# Motor-Driver-30A-1.net
KiCad netlist of a schematic drawn in EAGLE
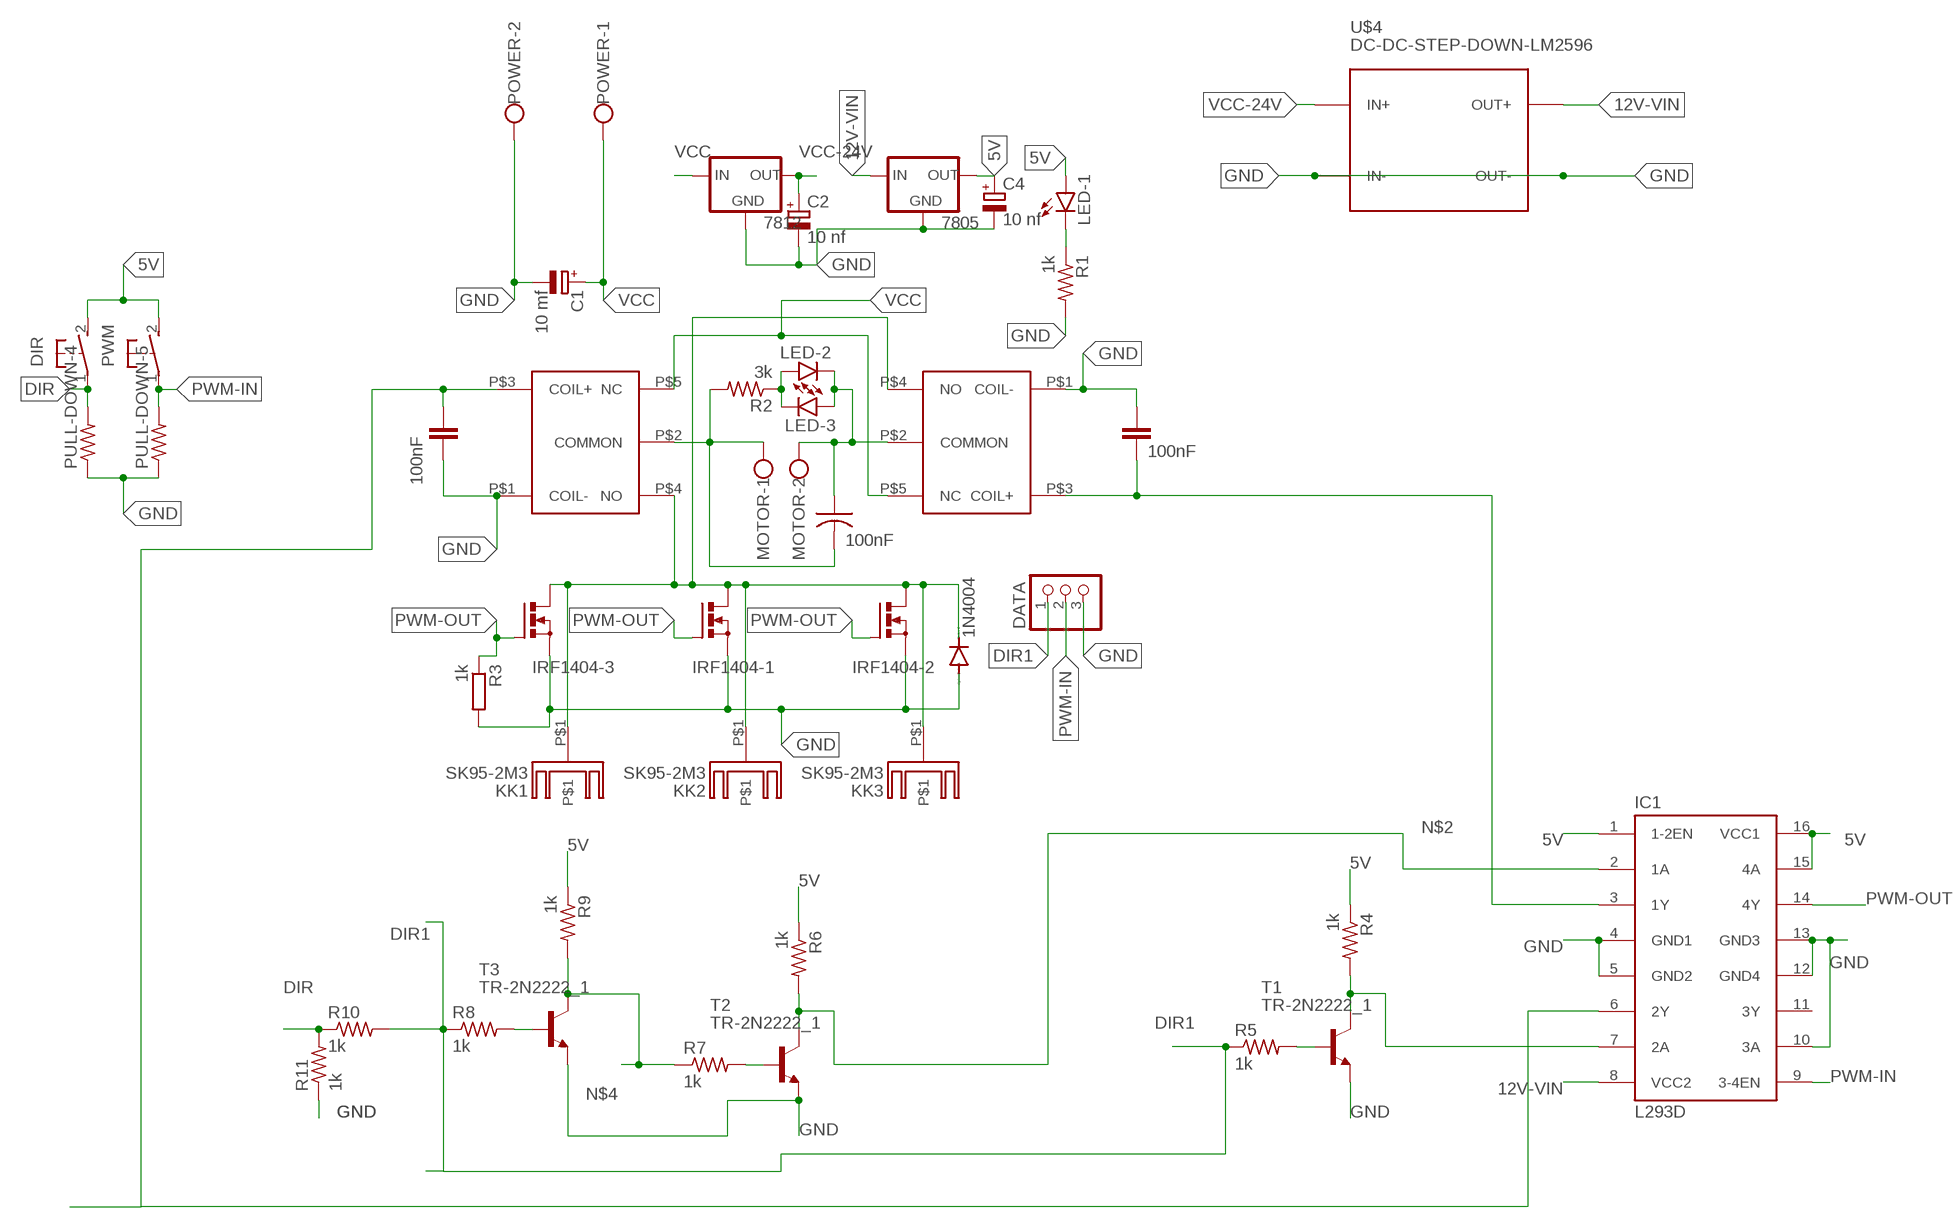
[diagram p0: schematic, sheet 1]

(export (version "E")
  (design (tool "Eeschema 10.0.6"))
  (components
    (comp (ref "7805")
      (value "78XXL")
      (footprint "eagle-import:78XXL")
      (libsource (lib "eagle-import") (part "v-reg_409_78XXL"))
    )
    (comp (ref "7812")
      (value "78XXL")
      (footprint "eagle-import:78XXL")
      (libsource (lib "eagle-import") (part "78XXL"))
    )
    (comp (ref "C1")
      (value "10 mf")
      (footprint "eagle-import:E2,5-7")
      (libsource (lib "eagle-import") (part "CPOL-EUE2.5-7"))
    )
    (comp (ref "C2")
      (value "10 nf")
      (footprint "eagle-import:E2,5-7")
      (libsource (lib "eagle-import") (part "CPOL-EUE2.5-7"))
    )
    (comp (ref "C4")
      (value "10 nf")
      (footprint "eagle-import:E2,5-7")
      (libsource (lib "eagle-import") (part "CPOL-EUE2.5-7"))
    )
    (comp (ref "DATA")
      (value "PINHD-3_DATA")
      (footprint "eagle-import:1X03_DATA")
      (libsource (lib "eagle-import") (part "PINHD-3_DATA"))
    )
    (comp (ref "DIR")
      (value "PUSHBOTTON")
      (footprint "eagle-import:B3F-10XX")
      (libsource (lib "eagle-import") (part "PUSHBOTTON"))
    )
    (comp (ref "IC1")
      (value "L293D")
      (footprint "eagle-import:DIL16")
      (libsource (lib "eagle-import") (part "L293D"))
    )
    (comp (ref "IRF1404-1")
      (value "PMOSFET_NTO220BV")
      (footprint "eagle-import:TO220BV")
      (libsource (lib "eagle-import") (part "PMOSFET_NTO220BV"))
    )
    (comp (ref "IRF1404-2")
      (value "PMOSFET_NTO220BV")
      (footprint "eagle-import:TO220BV")
      (libsource (lib "eagle-import") (part "PMOSFET_NTO220BV"))
    )
    (comp (ref "IRF1404-3")
      (value "PMOSFET_NTO220BV")
      (footprint "eagle-import:TO220BV")
      (libsource (lib "eagle-import") (part "PMOSFET_NTO220BV"))
    )
    (comp (ref "KK1")
      (value "SK95-2M3")
      (footprint "eagle-import:SK95-2M3")
      (libsource (lib "eagle-import") (part "SK95-2M3"))
    )
    (comp (ref "KK2")
      (value "SK95-2M3")
      (footprint "eagle-import:SK95-2M3")
      (libsource (lib "eagle-import") (part "SK95-2M3"))
    )
    (comp (ref "KK3")
      (value "SK95-2M3")
      (footprint "eagle-import:SK95-2M3")
      (libsource (lib "eagle-import") (part "SK95-2M3"))
    )
    (comp (ref "LED-1")
      (value "LED3MM")
      (footprint "eagle-import:LED3MM")
      (libsource (lib "eagle-import") (part "LED3MM"))
    )
    (comp (ref "LED-2")
      (value "LED3MM")
      (footprint "eagle-import:LED3MM")
      (libsource (lib "eagle-import") (part "LED3MM"))
    )
    (comp (ref "LED-3")
      (value "LED3MM")
      (footprint "eagle-import:LED3MM")
      (libsource (lib "eagle-import") (part "LED3MM"))
    )
    (comp (ref "MOTOR")
      (value "W239-302")
      (footprint "eagle-import:W239-302")
      (libsource (lib "eagle-import") (part "W239-302"))
    )
    (comp (ref "POWER")
      (value "W239-302")
      (footprint "eagle-import:W239-302")
      (libsource (lib "eagle-import") (part "W239-302"))
    )
    (comp (ref "PULL-DOWN-4")
      (value "R-US_0204/7")
      (footprint "eagle-import:0204_7")
      (libsource (lib "eagle-import") (part "R-US_0204/7"))
    )
    (comp (ref "PULL-DOWN-5")
      (value "R-US_0204/2V")
      (footprint "eagle-import:0204V")
      (libsource (lib "eagle-import") (part "R-US_0204/2V"))
    )
    (comp (ref "PWM")
      (value "PUSHBOTTON")
      (footprint "eagle-import:B3F-10XX")
      (libsource (lib "eagle-import") (part "PUSHBOTTON"))
    )
    (comp (ref "R1")
      (value "1k")
      (footprint "eagle-import:0204V")
      (libsource (lib "eagle-import") (part "R-US_0204/2V"))
    )
    (comp (ref "R2")
      (value "3k")
      (footprint "eagle-import:0207_10")
      (libsource (lib "eagle-import") (part "R-US_0207/10"))
    )
    (comp (ref "R3")
      (value "1k")
      (footprint "eagle-import:0204_7")
      (libsource (lib "eagle-import") (part "R-EU_0204/7"))
    )
    (comp (ref "R4")
      (value "1k")
      (footprint "eagle-import:0204_7")
      (libsource (lib "eagle-import") (part "R-US_0204/7"))
    )
    (comp (ref "R5")
      (value "1k")
      (footprint "eagle-import:0204_5")
      (libsource (lib "eagle-import") (part "R-US_0204/5"))
    )
    (comp (ref "R6")
      (value "1k")
      (footprint "eagle-import:0204_7")
      (libsource (lib "eagle-import") (part "R-US_0204/7"))
    )
    (comp (ref "R7")
      (value "1k")
      (footprint "eagle-import:0204V")
      (libsource (lib "eagle-import") (part "R-US_0204/2V"))
    )
    (comp (ref "R8")
      (value "1k")
      (footprint "eagle-import:0204_5")
      (libsource (lib "eagle-import") (part "R-US_0204/5"))
    )
    (comp (ref "R9")
      (value "1k")
      (footprint "eagle-import:0204_7")
      (libsource (lib "eagle-import") (part "R-US_0204/7"))
    )
    (comp (ref "R10")
      (value "1k")
      (footprint "eagle-import:0204V")
      (libsource (lib "eagle-import") (part "R-US_0204/2V"))
    )
    (comp (ref "R11")
      (value "1k")
      (footprint "eagle-import:0204V")
      (libsource (lib "eagle-import") (part "R-US_0204/2V"))
    )
    (comp (ref "REVERSE-CURRENT")
      (value "1N4004")
      (footprint "eagle-import:DO41-10")
      (libsource (lib "eagle-import") (part "1N4004"))
    )
    (comp (ref "T1")
      (value "TR-2N2222_1")
      (footprint "eagle-import:TO92-EBC")
      (libsource (lib "eagle-import") (part "TR-2N2222_1"))
    )
    (comp (ref "T2")
      (value "TR-2N2222_1")
      (footprint "eagle-import:TO92-EBC")
      (libsource (lib "eagle-import") (part "TR-2N2222_1"))
    )
    (comp (ref "T3")
      (value "TR-2N2222_1")
      (footprint "eagle-import:TO92-EBC")
      (libsource (lib "eagle-import") (part "TR-2N2222_1"))
    )
    (comp (ref "U$1")
      (value "RELAY-30A")
      (footprint "eagle-import:RELAY-30A")
      (libsource (lib "eagle-import") (part "RELAY-30A"))
    )
    (comp (ref "U$2")
      (value "RELAY-30A")
      (footprint "eagle-import:RELAY-30A")
      (libsource (lib "eagle-import") (part "RELAY-30A"))
    )
    (comp (ref "U$3")
      (value "100nF")
      (footprint "eagle-import:C025-025X050")
      (libsource (lib "eagle-import") (part "CAPACITOR"))
    )
    (comp (ref "U$4")
      (value "DC-DC-STEP-DOWN-LM2596")
      (footprint "eagle-import:DC-DC-STEP-DOWN-LM2596")
      (libsource (lib "eagle-import") (part "DC-DC-STEP-DOWN-LM2596"))
    )
    (comp (ref "U$5")
      (value "100nF")
      (footprint "eagle-import:C025-025X050")
      (libsource (lib "eagle-import") (part "CAPACITOR"))
    )
    (comp (ref "U$6")
      (value "100nF")
      (footprint "eagle-import:C075-032X103")
      (libsource (lib "eagle-import") (part "C-US075-032X103"))
    )
  )
  (nets
    (net (code "1") (name "/N$2") (class "Default")
      (node (ref "IC1") (pin "2") (pinfunction "1A_2") (pintype "input"))
      (node (ref "R6") (pin "2") (pinfunction "2_2") (pintype "passive"))
      (node (ref "T2") (pin "C") (pinfunction "C_C") (pintype "passive"))
    )
    (net (code "2") (name "/N$4") (class "Default")
      (node (ref "R7") (pin "1") (pinfunction "1_1") (pintype "passive"))
      (node (ref "R9") (pin "2") (pinfunction "2_2") (pintype "passive"))
      (node (ref "T3") (pin "C") (pinfunction "C_C") (pintype "passive"))
    )
    (net (code "3") (name "5V") (class "Default")
      (node (ref "7805") (pin "OUT") (pinfunction "OUT_OUT") (pintype "passive"))
      (node (ref "C4") (pin "+") (pinfunction "+_+") (pintype "passive"))
      (node (ref "DIR") (pin "2") (pinfunction "S_2") (pintype "passive"))
      (node (ref "IC1") (pin "1") (pinfunction "1-2EN_1") (pintype "input"))
      (node (ref "IC1") (pin "15") (pinfunction "4A_15") (pintype "input"))
      (node (ref "IC1") (pin "16") (pinfunction "VCC1_16") (pintype "power_in"))
      (node (ref "LED-1") (pin "A") (pinfunction "A_A") (pintype "passive"))
      (node (ref "PWM") (pin "2") (pinfunction "S_2") (pintype "passive"))
      (node (ref "R4") (pin "1") (pinfunction "1_1") (pintype "passive"))
      (node (ref "R6") (pin "1") (pinfunction "1_1") (pintype "passive"))
      (node (ref "R9") (pin "1") (pinfunction "1_1") (pintype "passive"))
    )
    (net (code "4") (name "12V-VIN") (class "Default")
      (node (ref "7805") (pin "IN") (pinfunction "IN_IN") (pintype "input"))
      (node (ref "IC1") (pin "8") (pinfunction "VCC2_8") (pintype "power_in"))
      (node (ref "U$4") (pin "OUT+") (pinfunction "OUT+_OUT+") (pintype "bidirectional"))
    )
    (net (code "5") (name "DIR") (class "Default")
      (node (ref "DIR") (pin "1") (pinfunction "P_1") (pintype "passive"))
      (node (ref "PULL-DOWN-4") (pin "2") (pinfunction "2_2") (pintype "passive"))
      (node (ref "R10") (pin "1") (pinfunction "1_1") (pintype "passive"))
      (node (ref "R11") (pin "2") (pinfunction "2_2") (pintype "passive"))
    )
    (net (code "6") (name "DIR1") (class "Default")
      (node (ref "DATA") (pin "1") (pinfunction "1_1") (pintype "passive"))
      (node (ref "R10") (pin "2") (pinfunction "2_2") (pintype "passive"))
      (node (ref "R5") (pin "1") (pinfunction "1_1") (pintype "passive"))
      (node (ref "R8") (pin "1") (pinfunction "1_1") (pintype "passive"))
    )
    (net (code "7") (name "GND") (class "Default")
      (node (ref "7805") (pin "GND") (pinfunction "GND_GND") (pintype "input"))
      (node (ref "7812") (pin "GND") (pinfunction "GND_GND") (pintype "input"))
      (node (ref "C1") (pin "-") (pinfunction "-_-") (pintype "passive"))
      (node (ref "C2") (pin "-") (pinfunction "-_-") (pintype "passive"))
      (node (ref "C4") (pin "-") (pinfunction "-_-") (pintype "passive"))
      (node (ref "DATA") (pin "3") (pinfunction "3_3") (pintype "passive"))
      (node (ref "IC1") (pin "10") (pinfunction "3A_10") (pintype "input"))
      (node (ref "IC1") (pin "12") (pinfunction "GND4_12") (pintype "power_in"))
      (node (ref "IC1") (pin "13") (pinfunction "GND3_13") (pintype "power_in"))
      (node (ref "IC1") (pin "4") (pinfunction "GND1_4") (pintype "power_in"))
      (node (ref "IC1") (pin "5") (pinfunction "GND2_5") (pintype "power_in"))
      (node (ref "IRF1404-1") (pin "S") (pinfunction "S_S") (pintype "passive"))
      (node (ref "IRF1404-2") (pin "S") (pinfunction "S_S") (pintype "passive"))
      (node (ref "IRF1404-3") (pin "S") (pinfunction "S_S") (pintype "passive"))
      (node (ref "POWER") (pin "2") (pinfunction "KL_2") (pintype "passive"))
      (node (ref "PULL-DOWN-4") (pin "1") (pinfunction "1_1") (pintype "passive"))
      (node (ref "PULL-DOWN-5") (pin "1") (pinfunction "1_1") (pintype "passive"))
      (node (ref "R1") (pin "2") (pinfunction "2_2") (pintype "passive"))
      (node (ref "R11") (pin "1") (pinfunction "1_1") (pintype "passive"))
      (node (ref "R3") (pin "2") (pinfunction "2_2") (pintype "passive"))
      (node (ref "REVERSE-CURRENT") (pin "A") (pinfunction "A_A") (pintype "passive"))
      (node (ref "T1") (pin "E") (pinfunction "E_E") (pintype "passive"))
      (node (ref "T2") (pin "E") (pinfunction "E_E") (pintype "passive"))
      (node (ref "T3") (pin "E") (pinfunction "E_E") (pintype "passive"))
      (node (ref "U$1") (pin "P$1") (pinfunction "COIL-_P$1") (pintype "bidirectional"))
      (node (ref "U$2") (pin "P$1") (pinfunction "COIL-_P$1") (pintype "bidirectional"))
      (node (ref "U$3") (pin "2") (pinfunction "2_2") (pintype "passive"))
      (node (ref "U$4") (pin "IN-") (pinfunction "IN-_IN-") (pintype "bidirectional"))
      (node (ref "U$4") (pin "OUT-") (pinfunction "OUT-_OUT-") (pintype "bidirectional"))
      (node (ref "U$5") (pin "1") (pinfunction "1_1") (pintype "passive"))
    )
    (net (code "8") (name "Net-(IC1-1Y)") (class "Default")
      (node (ref "IC1") (pin "3") (pinfunction "1Y_3") (pintype "output"))
      (node (ref "U$2") (pin "P$3") (pinfunction "COIL+_P$3") (pintype "bidirectional"))
      (node (ref "U$5") (pin "2") (pinfunction "2_2") (pintype "passive"))
    )
    (net (code "9") (name "Net-(IC1-2A)") (class "Default")
      (node (ref "IC1") (pin "7") (pinfunction "2A_7") (pintype "input"))
      (node (ref "R4") (pin "2") (pinfunction "2_2") (pintype "passive"))
      (node (ref "T1") (pin "C") (pinfunction "C_C") (pintype "passive"))
    )
    (net (code "10") (name "Net-(IC1-2Y)") (class "Default")
      (node (ref "IC1") (pin "6") (pinfunction "2Y_6") (pintype "output"))
      (node (ref "U$1") (pin "P$3") (pinfunction "COIL+_P$3") (pintype "bidirectional"))
      (node (ref "U$3") (pin "1") (pinfunction "1_1") (pintype "passive"))
    )
    (net (code "11") (name "Net-(LED-1-C)") (class "Default")
      (node (ref "LED-1") (pin "K") (pinfunction "C_K") (pintype "passive"))
      (node (ref "R1") (pin "1") (pinfunction "1_1") (pintype "passive"))
    )
    (net (code "12") (name "Net-(LED-2-C)") (class "Default")
      (node (ref "LED-2") (pin "K") (pinfunction "C_K") (pintype "passive"))
      (node (ref "LED-3") (pin "A") (pinfunction "A_A") (pintype "passive"))
      (node (ref "MOTOR") (pin "2") (pinfunction "KL_2") (pintype "passive"))
      (node (ref "U$2") (pin "P$2") (pinfunction "COMMON_P$2") (pintype "bidirectional"))
      (node (ref "U$6") (pin "1") (pinfunction "1_1") (pintype "passive"))
    )
    (net (code "13") (name "Net-(LED-3-C)") (class "Default")
      (node (ref "LED-2") (pin "A") (pinfunction "A_A") (pintype "passive"))
      (node (ref "LED-3") (pin "K") (pinfunction "C_K") (pintype "passive"))
      (node (ref "R2") (pin "1") (pinfunction "1_1") (pintype "passive"))
    )
    (net (code "14") (name "Net-(MOTORA-KL)") (class "Default")
      (node (ref "MOTOR") (pin "1") (pinfunction "KL_1") (pintype "passive"))
      (node (ref "R2") (pin "2") (pinfunction "2_2") (pintype "passive"))
      (node (ref "U$1") (pin "P$2") (pinfunction "COMMON_P$2") (pintype "bidirectional"))
      (node (ref "U$6") (pin "2") (pinfunction "2_2") (pintype "passive"))
    )
    (net (code "15") (name "Net-(R5-Pad2)") (class "Default")
      (node (ref "R5") (pin "2") (pinfunction "2_2") (pintype "passive"))
      (node (ref "T1") (pin "B") (pinfunction "B_B") (pintype "passive"))
    )
    (net (code "16") (name "Net-(R7-Pad2)") (class "Default")
      (node (ref "R7") (pin "2") (pinfunction "2_2") (pintype "passive"))
      (node (ref "T2") (pin "B") (pinfunction "B_B") (pintype "passive"))
    )
    (net (code "17") (name "Net-(R8-Pad2)") (class "Default")
      (node (ref "R8") (pin "2") (pinfunction "2_2") (pintype "passive"))
      (node (ref "T3") (pin "B") (pinfunction "B_B") (pintype "passive"))
    )
    (net (code "18") (name "Net-(U$1-NO)") (class "Default")
      (node (ref "IRF1404-1") (pin "D") (pinfunction "D_D") (pintype "passive"))
      (node (ref "IRF1404-2") (pin "D") (pinfunction "D_D") (pintype "passive"))
      (node (ref "IRF1404-3") (pin "D") (pinfunction "D_D") (pintype "passive"))
      (node (ref "KK1") (pin "P$1") (pinfunction "P$1_P$1") (pintype "bidirectional"))
      (node (ref "KK2") (pin "P$1") (pinfunction "P$1_P$1") (pintype "bidirectional"))
      (node (ref "KK3") (pin "P$1") (pinfunction "P$1_P$1") (pintype "bidirectional"))
      (node (ref "REVERSE-CURRENT") (pin "C") (pinfunction "C_C") (pintype "passive"))
      (node (ref "U$1") (pin "P$4") (pinfunction "NO_P$4") (pintype "bidirectional"))
      (node (ref "U$2") (pin "P$4") (pinfunction "NO_P$4") (pintype "bidirectional"))
    )
    (net (code "19") (name "PWM-IN") (class "Default")
      (node (ref "DATA") (pin "2") (pinfunction "2_2") (pintype "passive"))
      (node (ref "IC1") (pin "9") (pinfunction "3-4EN_9") (pintype "input"))
      (node (ref "PULL-DOWN-5") (pin "2") (pinfunction "2_2") (pintype "passive"))
      (node (ref "PWM") (pin "1") (pinfunction "P_1") (pintype "passive"))
    )
    (net (code "20") (name "PWM-OUT") (class "Default")
      (node (ref "IC1") (pin "14") (pinfunction "4Y_14") (pintype "output"))
      (node (ref "IRF1404-1") (pin "G") (pinfunction "G_G") (pintype "passive"))
      (node (ref "IRF1404-2") (pin "G") (pinfunction "G_G") (pintype "passive"))
      (node (ref "IRF1404-3") (pin "G") (pinfunction "G_G") (pintype "passive"))
      (node (ref "R3") (pin "1") (pinfunction "1_1") (pintype "passive"))
    )
    (net (code "21") (name "VCC") (class "Default")
      (node (ref "7812") (pin "IN") (pinfunction "IN_IN") (pintype "input"))
      (node (ref "C1") (pin "+") (pinfunction "+_+") (pintype "passive"))
      (node (ref "POWER") (pin "1") (pinfunction "KL_1") (pintype "passive"))
      (node (ref "U$1") (pin "P$5") (pinfunction "NC_P$5") (pintype "bidirectional"))
      (node (ref "U$2") (pin "P$5") (pinfunction "NC_P$5") (pintype "bidirectional"))
    )
    (net (code "22") (name "VCC-24V") (class "Default")
      (node (ref "7812") (pin "OUT") (pinfunction "OUT_OUT") (pintype "passive"))
      (node (ref "C2") (pin "+") (pinfunction "+_+") (pintype "passive"))
      (node (ref "U$4") (pin "IN+") (pinfunction "IN+_IN+") (pintype "bidirectional"))
    )
    (net (code "23") (name "unconnected-(IC1-3Y-Pad11)") (class "Default")
      (node (ref "IC1") (pin "11") (pinfunction "3Y_11") (pintype "output"))
    )
  )
)
